# Recorder.net
KiCad netlist of a schematic drawn in EAGLE
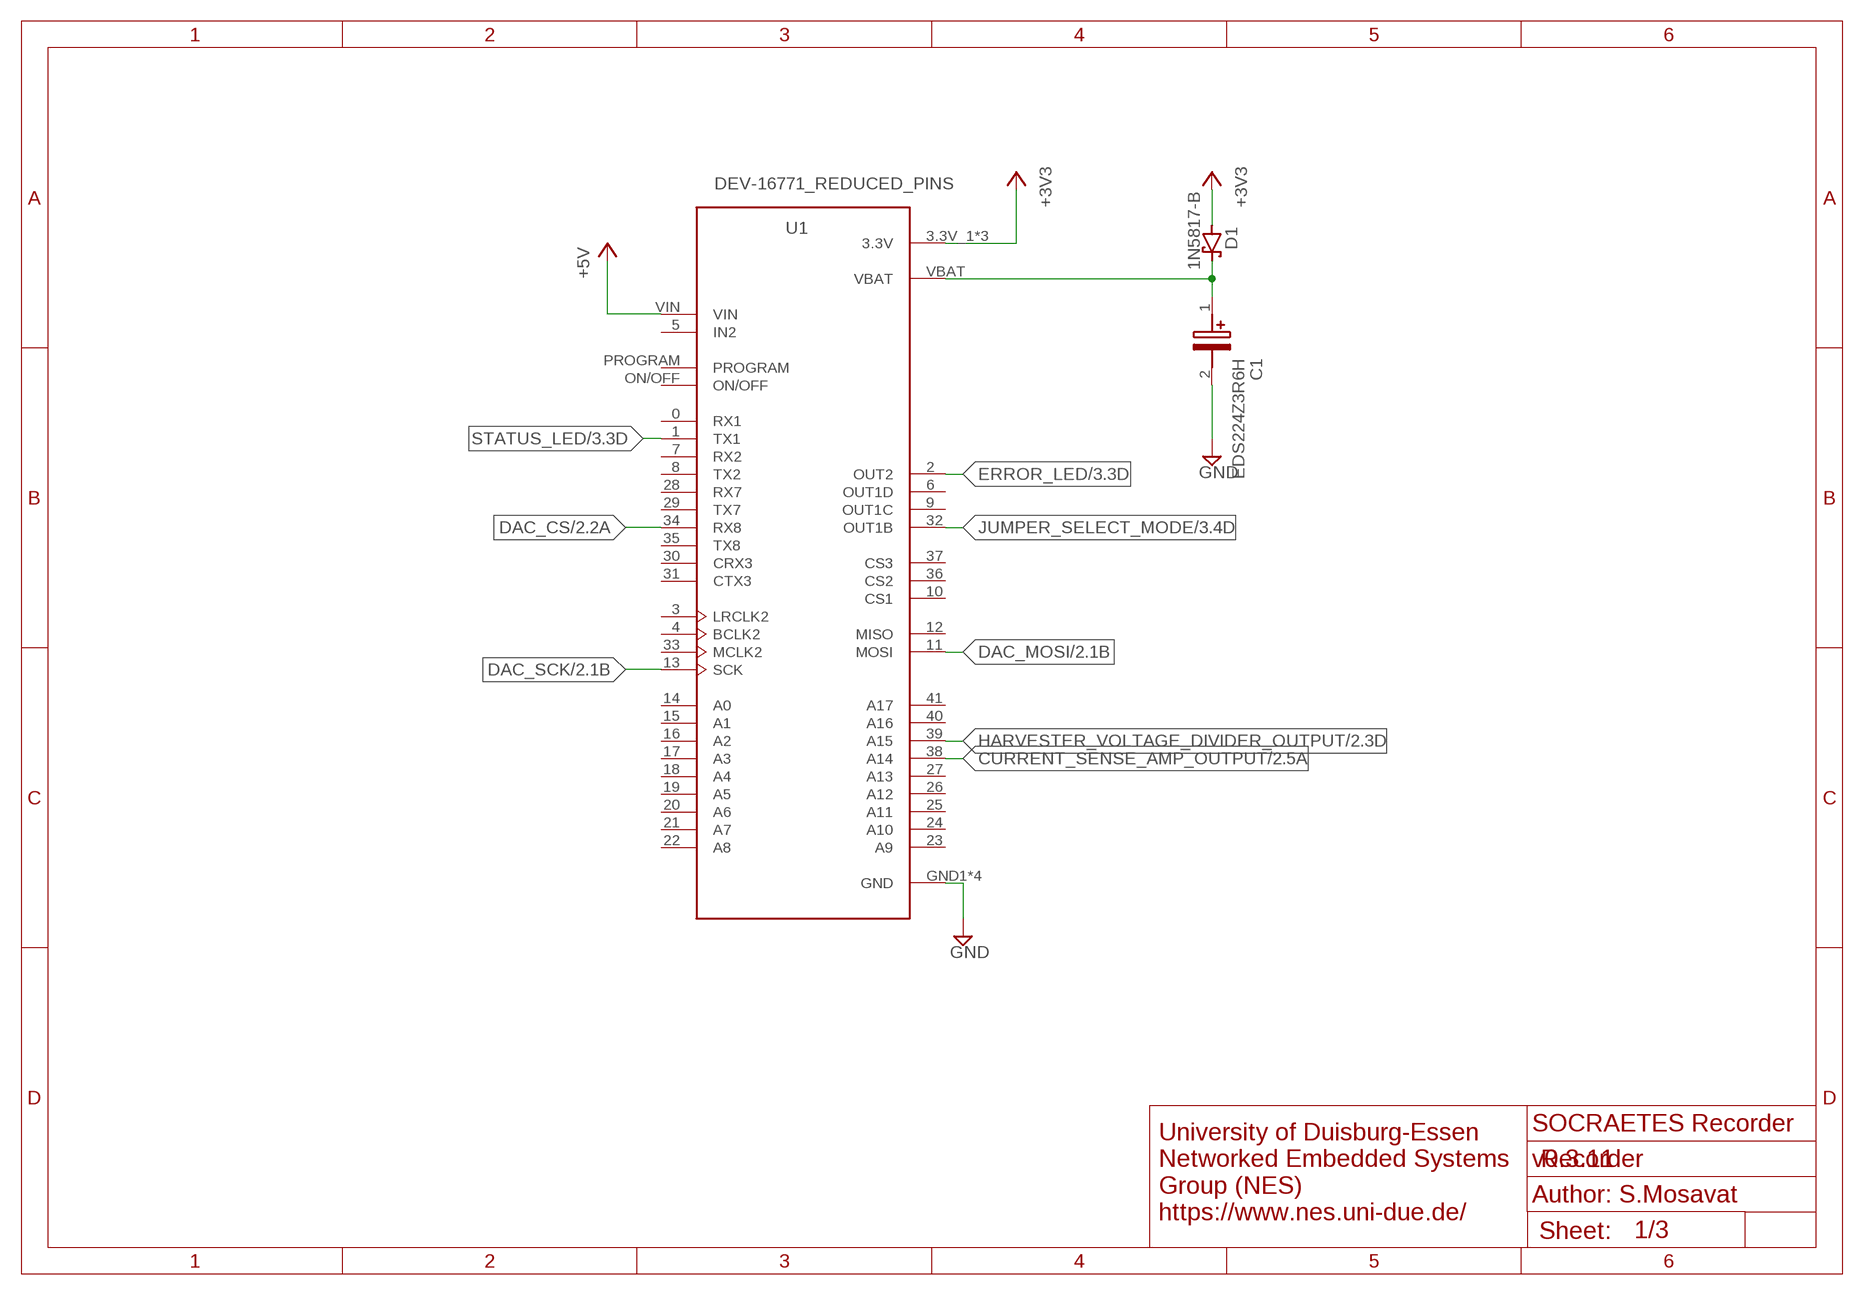
[diagram p0: schematic, sheet 1]
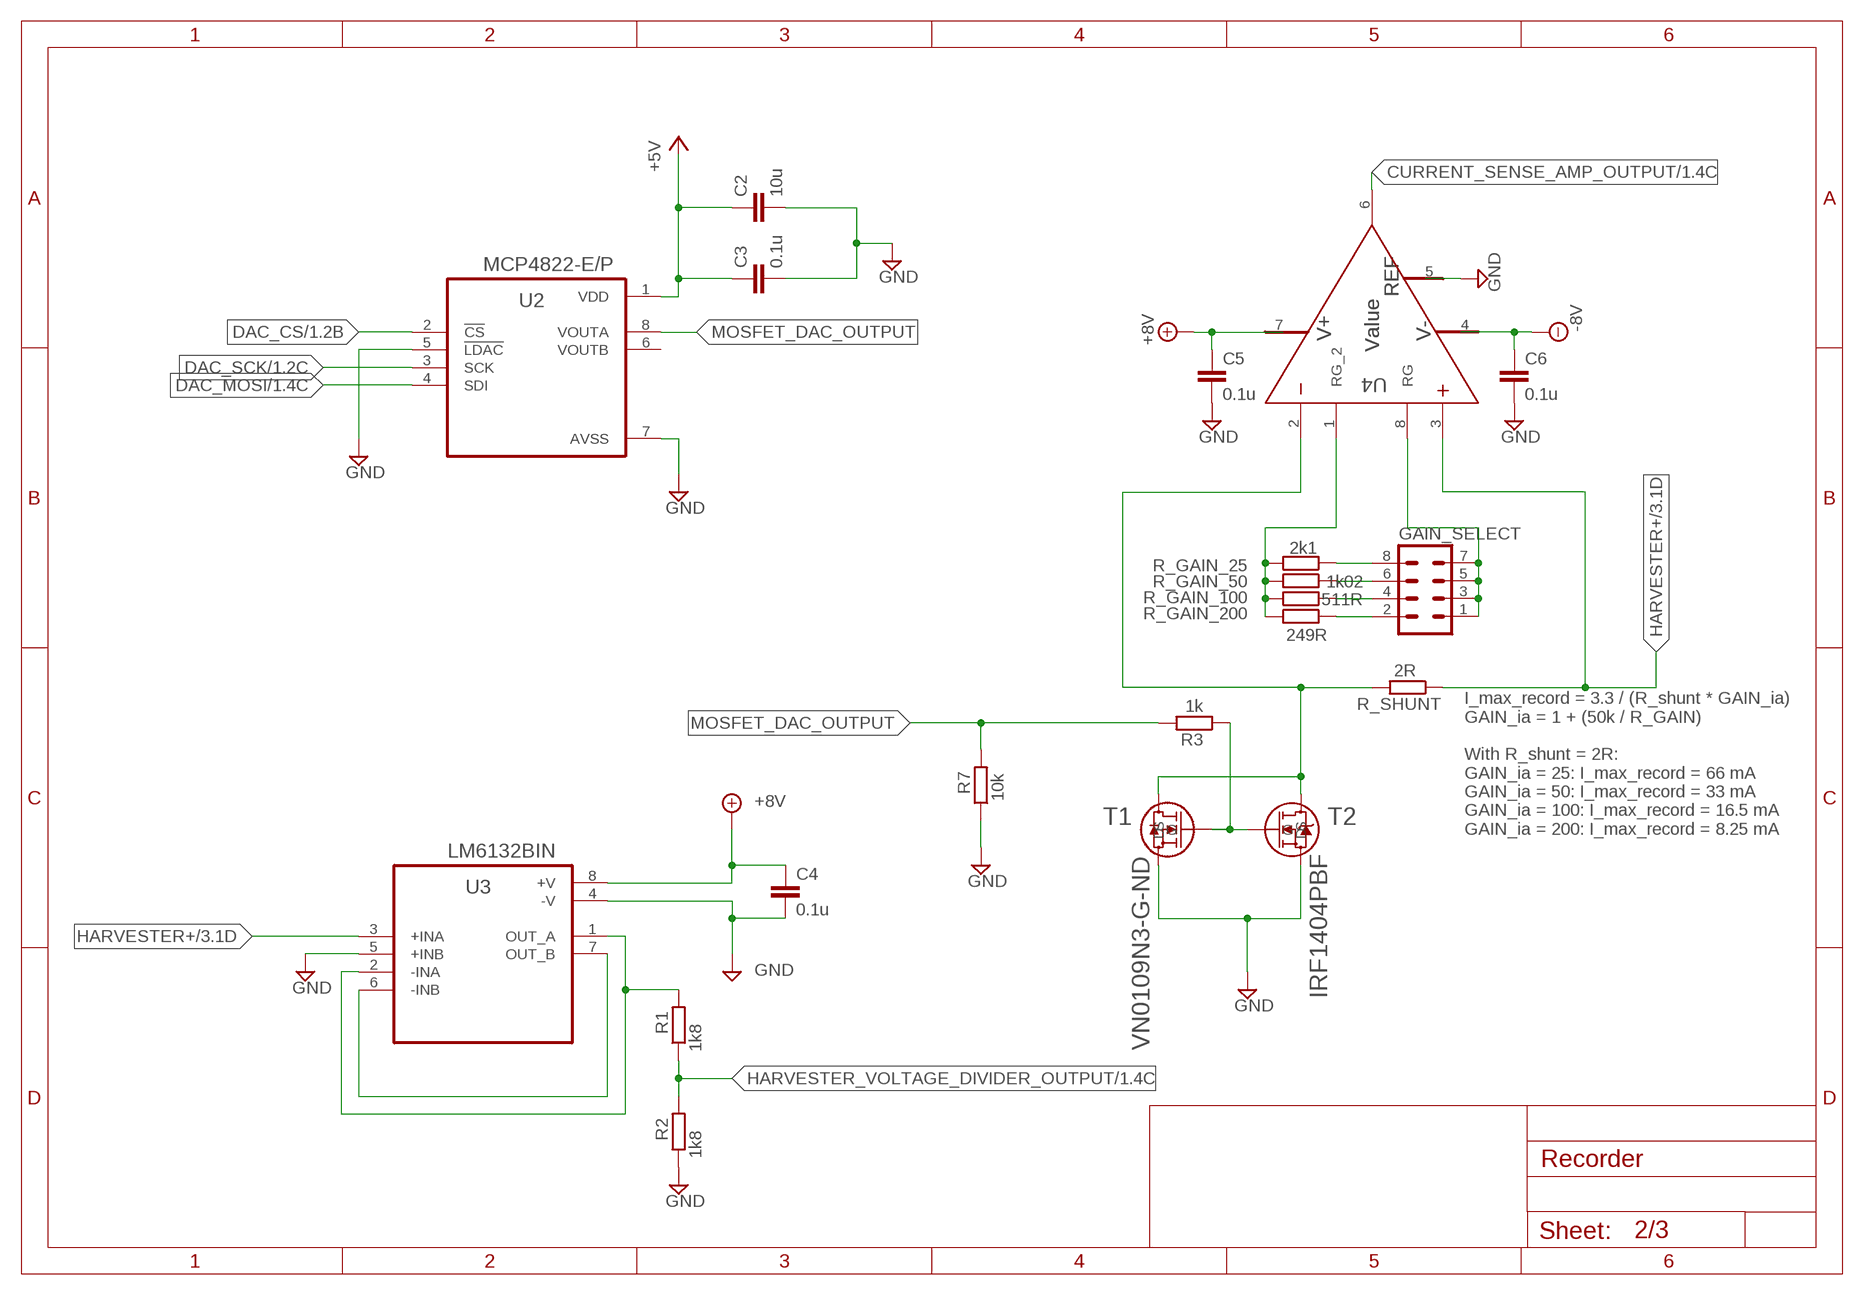
[diagram p1: schematic, sheet 2]
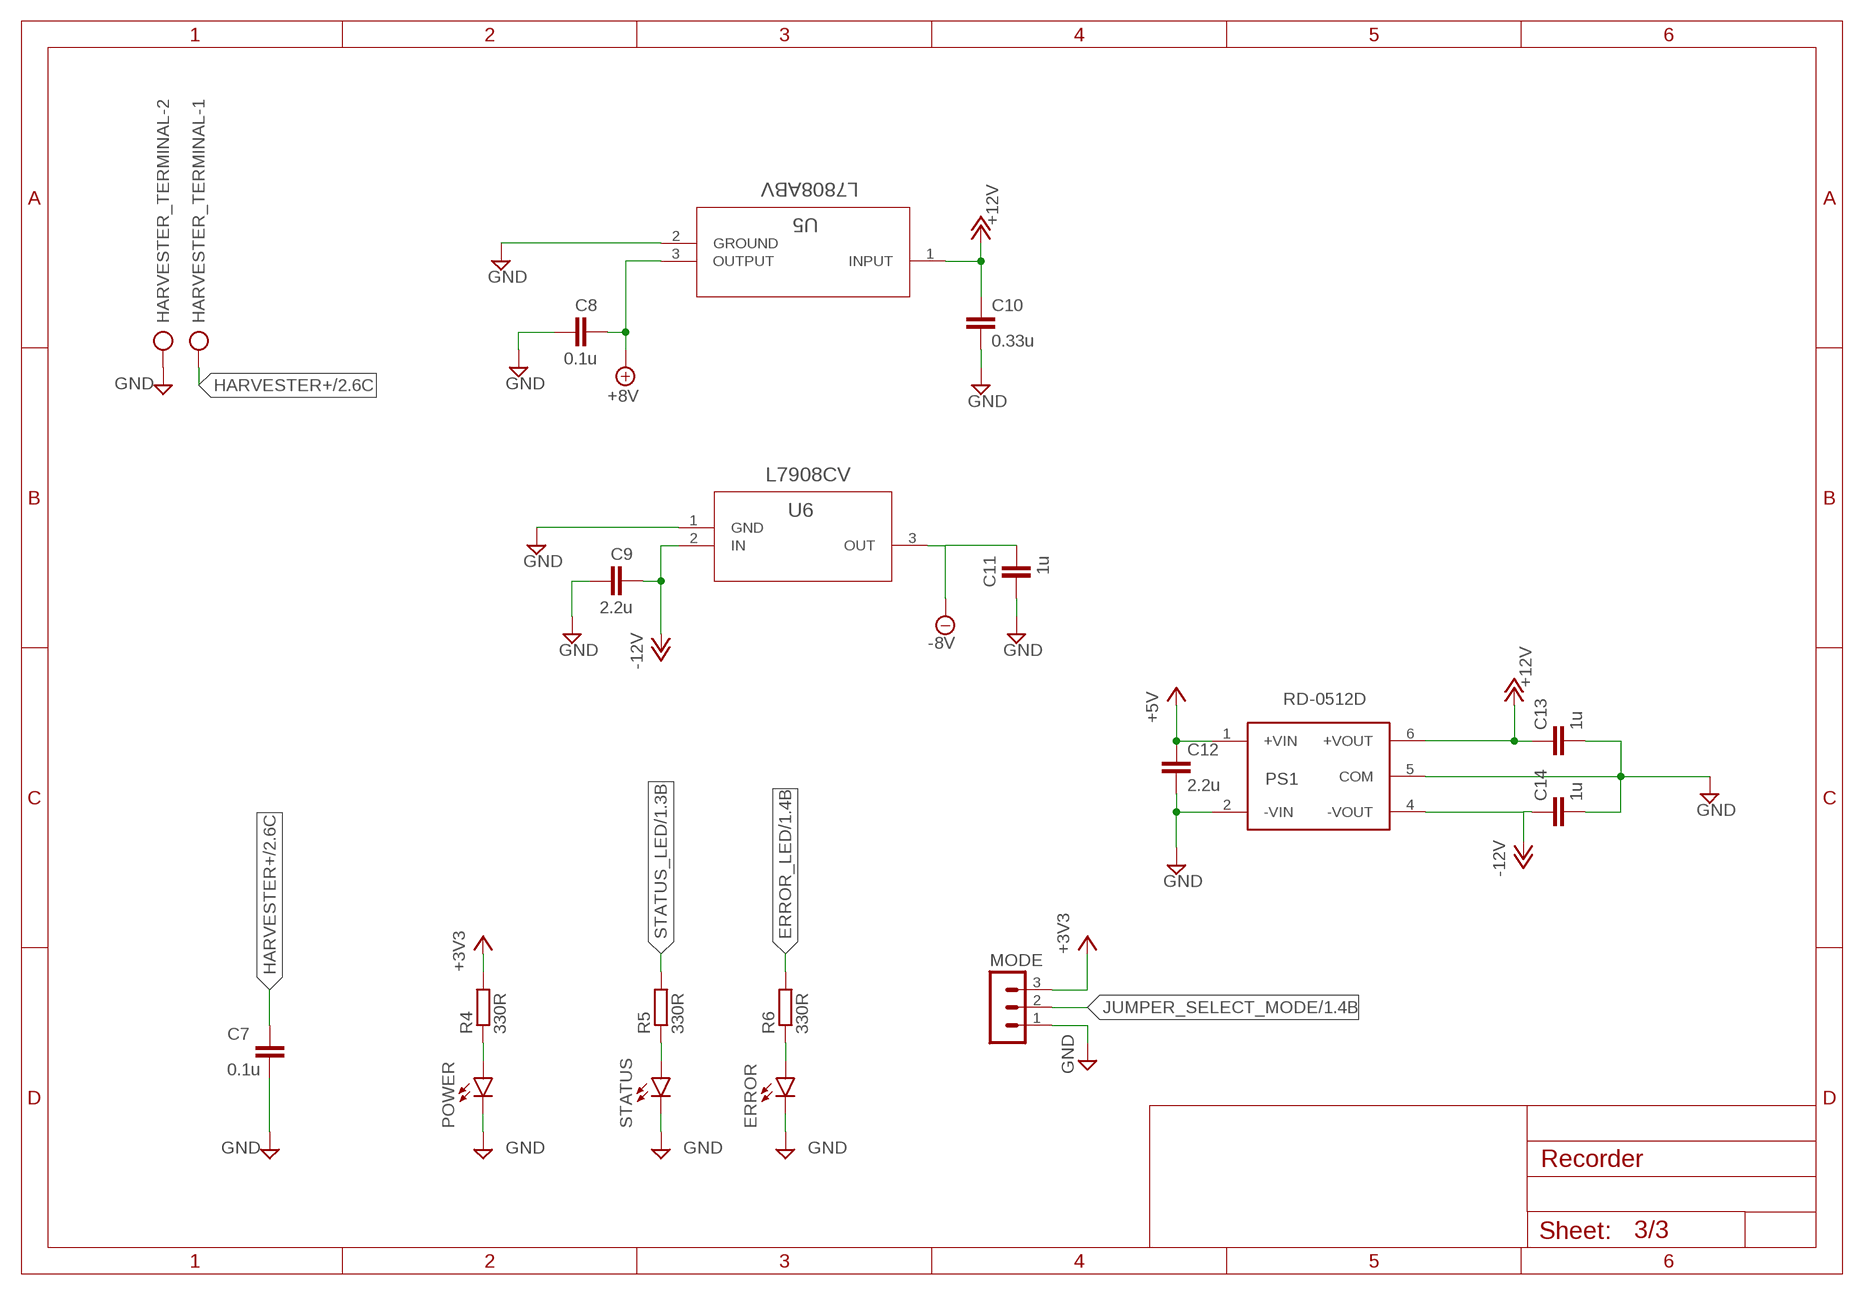
[diagram p2: schematic, sheet 3]

(export (version "E")
  (design (tool "Eeschema 10.0.6"))
  (components
    (comp (ref "C2")
      (value "10u")
      (footprint "eagle-import:C025-024X044")
      (libsource (lib "eagle-import") (part "C-EU025-024X044"))
    )
    (comp (ref "C3")
      (value "0.1u")
      (footprint "eagle-import:C025-024X044")
      (libsource (lib "eagle-import") (part "C-EU025-024X044"))
    )
    (comp (ref "C4")
      (value "0.1u")
      (footprint "eagle-import:C025-024X044")
      (libsource (lib "eagle-import") (part "C-EU025-024X044"))
    )
    (comp (ref "C5")
      (value "0.1u")
      (footprint "eagle-import:C025-024X044")
      (libsource (lib "eagle-import") (part "C-EU025-024X044"))
    )
    (comp (ref "C6")
      (value "0.1u")
      (footprint "eagle-import:C025-024X044")
      (libsource (lib "eagle-import") (part "C-EU025-024X044"))
    )
    (comp (ref "GAIN_SELECT")
      (value "MA04-2")
      (footprint "eagle-import:MA04-2")
      (libsource (lib "eagle-import") (part "MA04-2"))
    )
    (comp (ref "R1")
      (value "1k8")
      (footprint "eagle-import:0207_10")
      (libsource (lib "eagle-import") (part "R-EU_0207/10"))
    )
    (comp (ref "R2")
      (value "1k8")
      (footprint "eagle-import:0207_10")
      (libsource (lib "eagle-import") (part "R-EU_0207/10"))
    )
    (comp (ref "R3")
      (value "1k")
      (footprint "eagle-import:0207_10")
      (libsource (lib "eagle-import") (part "R-EU_0207/10"))
    )
    (comp (ref "R7")
      (value "10k")
      (footprint "eagle-import:0207_10")
      (libsource (lib "eagle-import") (part "R-EU_0207/10"))
    )
    (comp (ref "R_GAIN_25")
      (value "2k1")
      (footprint "eagle-import:0207_10")
      (libsource (lib "eagle-import") (part "R-EU_0207/10"))
    )
    (comp (ref "R_GAIN_50")
      (value "1k02")
      (footprint "eagle-import:0207_10")
      (libsource (lib "eagle-import") (part "R-EU_0207/10"))
    )
    (comp (ref "R_GAIN_100")
      (value "511R")
      (footprint "eagle-import:0207_10")
      (libsource (lib "eagle-import") (part "R-EU_0207/10"))
    )
    (comp (ref "R_GAIN_200")
      (value "249R")
      (footprint "eagle-import:0207_10")
      (libsource (lib "eagle-import") (part "R-EU_0207/10"))
    )
    (comp (ref "R_SHUNT")
      (value "2R")
      (footprint "eagle-import:0207_10")
      (libsource (lib "eagle-import") (part "R-EU_0207/10"))
    )
    (comp (ref "T1")
      (value "VN0109N3-G-ND")
      (footprint "eagle-import:TO92-CBE")
      (libsource (lib "eagle-import") (part "VN0109N3-G-ND"))
    )
    (comp (ref "T2")
      (value "IRF1404PBF")
      (footprint "eagle-import:PG-TO220-3-904_INF")
      (fields (field (name "COPYRIGHT") "Copyright (C) 2023 Ultra Librarian. All rights reserved."))
      (libsource (lib "eagle-import") (part "IRF1404PBF"))
    )
    (comp (ref "U2")
      (value "MCP4822-E/P")
      (footprint "eagle-import:DIP787W46P254L927H533Q8")
      (fields (field (name "MF") "Microchip"))
      (libsource (lib "eagle-import") (part "MCP4822-E/P"))
    )
    (comp (ref "U3")
      (value "LM6132BIN")
      (footprint "eagle-import:DIP794W45P254L959H508Q8")
      (fields
        (field (name "DIGI-KEY_PART_NUMBER") "LM6132BIN/NOPB-ND")
        (field (name "MF") "Texas Instruments")
        (field (name "MP") "LM6132BIN/NOPB")
      )
      (libsource (lib "eagle-import") (part "LM6132BIN"))
    )
    (comp (ref "U4")
      (value "Value")
      (footprint "eagle-import:P0008A")
      (fields (field (name "MANUFACTURER") "Texas Instruments") (field (name "PARTNUMBER") "INA121P"))
      (libsource (lib "eagle-import") (part "INA121PA"))
    )
    (comp (ref "C1")
      (value "EDS224Z3R6H")
      (footprint "eagle-import:EDS224Z3R6H")
      (fields (field (name "MOUSER_PART_NUMBER") "598-EDS224Z3R6H"))
      (libsource (lib "eagle-import") (part "EDS224Z3R6H"))
    )
    (comp (ref "D1")
      (value "1N5817-B")
      (footprint "eagle-import:DO41-7.6")
      (libsource (lib "eagle-import") (part "1N5817-B"))
    )
    (comp (ref "U1")
      (value "DEV-16771_REDUCED_PINS")
      (footprint "eagle-import:MODULE_DEV-16771_REDUCED_PINS")
      (libsource (lib "eagle-import") (part "DEV-16771_REDUCED_PINS"))
    )
    (comp (ref "C7")
      (value "0.1u")
      (footprint "eagle-import:C025-024X044")
      (libsource (lib "eagle-import") (part "C-EU025-024X044"))
    )
    (comp (ref "C8")
      (value "0.1u")
      (footprint "eagle-import:C025-024X044")
      (libsource (lib "eagle-import") (part "C-EU025-024X044"))
    )
    (comp (ref "C9")
      (value "2.2u")
      (footprint "eagle-import:C025-024X044")
      (libsource (lib "eagle-import") (part "C-EU025-024X044"))
    )
    (comp (ref "C10")
      (value "0.33u")
      (footprint "eagle-import:C025-024X044")
      (libsource (lib "eagle-import") (part "C-EU025-024X044"))
    )
    (comp (ref "C11")
      (value "1u")
      (footprint "eagle-import:C025-024X044")
      (libsource (lib "eagle-import") (part "C-EU025-024X044"))
    )
    (comp (ref "C12")
      (value "2.2u")
      (footprint "eagle-import:C025-024X044")
      (libsource (lib "eagle-import") (part "C-EU025-024X044"))
    )
    (comp (ref "C13")
      (value "1u")
      (footprint "eagle-import:C025-024X044")
      (libsource (lib "eagle-import") (part "C-EU025-024X044"))
    )
    (comp (ref "C14")
      (value "1u")
      (footprint "eagle-import:C025-024X044")
      (libsource (lib "eagle-import") (part "C-EU025-024X044"))
    )
    (comp (ref "ERROR")
      (value "LED5MM")
      (footprint "eagle-import:LED5MM")
      (libsource (lib "eagle-import") (part "LED5MM"))
    )
    (comp (ref "HARVESTER_TERMINAL")
      (value "AK300/2")
      (footprint "eagle-import:AK300_2")
      (libsource (lib "eagle-import") (part "AK300/2"))
    )
    (comp (ref "MODE")
      (value "MA03-1")
      (footprint "eagle-import:MA03-1")
      (libsource (lib "eagle-import") (part "MA03-1"))
    )
    (comp (ref "POWER")
      (value "LED5MM")
      (footprint "eagle-import:LED5MM")
      (libsource (lib "eagle-import") (part "LED5MM"))
    )
    (comp (ref "PS1")
      (value "RD-0512D")
      (footprint "eagle-import:CONV_RD-0512D")
      (fields (field (name "MF") "Recom Power"))
      (libsource (lib "eagle-import") (part "RD-0512D"))
    )
    (comp (ref "R4")
      (value "330R")
      (footprint "eagle-import:0207_10")
      (libsource (lib "eagle-import") (part "R-EU_0207/10"))
    )
    (comp (ref "R5")
      (value "330R")
      (footprint "eagle-import:0207_10")
      (libsource (lib "eagle-import") (part "R-EU_0207/10"))
    )
    (comp (ref "R6")
      (value "330R")
      (footprint "eagle-import:0207_10")
      (libsource (lib "eagle-import") (part "R-EU_0207/10"))
    )
    (comp (ref "STATUS")
      (value "LED5MM")
      (footprint "eagle-import:LED5MM")
      (libsource (lib "eagle-import") (part "LED5MM"))
    )
    (comp (ref "U5")
      (value "L7808ABV")
      (footprint "eagle-import:TO-220_STM")
      (libsource (lib "eagle-import") (part "L7808ABV"))
    )
    (comp (ref "U6")
      (value "L7908CV")
      (footprint "eagle-import:TO-220_STM")
      (libsource (lib "eagle-import") (part "L7908CV"))
    )
  )
  (nets
    (net (code "1") (name "+3V3") (class "Default")
      (node (ref "D1") (pin "A") (pinfunction "A_A") (pintype "passive"))
      (node (ref "MODE") (pin "3") (pinfunction "3_3") (pintype "passive"))
      (node (ref "R4") (pin "2") (pinfunction "2_2") (pintype "passive"))
      (node (ref "U1") (pin "3.3V_1") (pinfunction "3.3V_3.3V_1") (pintype "power_in"))
      (node (ref "U1") (pin "3.3V_2") (pinfunction "3.3V_3.3V_2") (pintype "power_in"))
      (node (ref "U1") (pin "3.3V_3") (pinfunction "3.3V_3.3V_3") (pintype "power_in"))
    )
    (net (code "2") (name "+5V") (class "Default")
      (node (ref "C12") (pin "1") (pinfunction "1_1") (pintype "passive"))
      (node (ref "C2") (pin "1") (pinfunction "1_1") (pintype "passive"))
      (node (ref "C3") (pin "1") (pinfunction "1_1") (pintype "passive"))
      (node (ref "PS1") (pin "1") (pinfunction "+VIN_1") (pintype "input"))
      (node (ref "U1") (pin "VIN") (pinfunction "VIN_VIN") (pintype "input"))
      (node (ref "U2") (pin "1") (pinfunction "VDD_1") (pintype "power_in"))
    )
    (net (code "3") (name "+8V") (class "Default")
      (node (ref "C4") (pin "1") (pinfunction "1_1") (pintype "passive"))
      (node (ref "C5") (pin "1") (pinfunction "1_1") (pintype "passive"))
      (node (ref "C8") (pin "2") (pinfunction "2_2") (pintype "passive"))
      (node (ref "U3") (pin "8") (pinfunction "+V_8") (pintype "power_in"))
      (node (ref "U4") (pin "7") (pinfunction "V+_7") (pintype "power_in"))
      (node (ref "U5") (pin "3") (pinfunction "OUTPUT_3") (pintype "output"))
    )
    (net (code "4") (name "+12V") (class "Default")
      (node (ref "C10") (pin "1") (pinfunction "1_1") (pintype "passive"))
      (node (ref "C13") (pin "1") (pinfunction "1_1") (pintype "passive"))
      (node (ref "PS1") (pin "6") (pinfunction "+VOUT_6") (pintype "output"))
      (node (ref "U5") (pin "1") (pinfunction "INPUT_1") (pintype "input"))
    )
    (net (code "5") (name "-8V") (class "Default")
      (node (ref "C11") (pin "2") (pinfunction "2_2") (pintype "passive"))
      (node (ref "C6") (pin "1") (pinfunction "1_1") (pintype "passive"))
      (node (ref "U4") (pin "4") (pinfunction "V-_4") (pintype "power_in"))
      (node (ref "U6") (pin "3") (pinfunction "OUT_3") (pintype "power_in"))
    )
    (net (code "6") (name "-12V") (class "Default")
      (node (ref "C14") (pin "1") (pinfunction "1_1") (pintype "passive"))
      (node (ref "C9") (pin "2") (pinfunction "2_2") (pintype "passive"))
      (node (ref "PS1") (pin "4") (pinfunction "-VOUT_4") (pintype "output"))
      (node (ref "U6") (pin "2") (pinfunction "IN_2") (pintype "power_in"))
    )
    (net (code "7") (name "CURRENT_SENSE_AMP_OUTPUT") (class "Default")
      (node (ref "U1") (pin "38") (pinfunction "A14_38") (pintype "bidirectional"))
      (node (ref "U4") (pin "6") (pinfunction "OUT_6") (pintype "output"))
    )
    (net (code "8") (name "DAC_CS") (class "Default")
      (node (ref "U1") (pin "34") (pinfunction "RX8_34") (pintype "bidirectional"))
      (node (ref "U2") (pin "2") (pinfunction "~{CS}_2") (pintype "input"))
    )
    (net (code "9") (name "DAC_MOSI") (class "Default")
      (node (ref "U1") (pin "11") (pinfunction "MOSI_11") (pintype "bidirectional"))
      (node (ref "U2") (pin "4") (pinfunction "SDI_4") (pintype "input"))
    )
    (net (code "10") (name "DAC_SCK") (class "Default")
      (node (ref "U1") (pin "13") (pinfunction "SCK_13") (pintype "bidirectional"))
      (node (ref "U2") (pin "3") (pinfunction "SCK_3") (pintype "input"))
    )
    (net (code "11") (name "ERROR_LED") (class "Default")
      (node (ref "R6") (pin "2") (pinfunction "2_2") (pintype "passive"))
      (node (ref "U1") (pin "2") (pinfunction "OUT2_2") (pintype "output"))
    )
    (net (code "12") (name "GND") (class "Default")
      (node (ref "C1") (pin "2") (pinfunction "-_2") (pintype "bidirectional"))
      (node (ref "C10") (pin "2") (pinfunction "2_2") (pintype "passive"))
      (node (ref "C11") (pin "1") (pinfunction "1_1") (pintype "passive"))
      (node (ref "C12") (pin "2") (pinfunction "2_2") (pintype "passive"))
      (node (ref "C13") (pin "2") (pinfunction "2_2") (pintype "passive"))
      (node (ref "C14") (pin "2") (pinfunction "2_2") (pintype "passive"))
      (node (ref "C2") (pin "2") (pinfunction "2_2") (pintype "passive"))
      (node (ref "C3") (pin "2") (pinfunction "2_2") (pintype "passive"))
      (node (ref "C4") (pin "2") (pinfunction "2_2") (pintype "passive"))
      (node (ref "C5") (pin "2") (pinfunction "2_2") (pintype "passive"))
      (node (ref "C6") (pin "2") (pinfunction "2_2") (pintype "passive"))
      (node (ref "C7") (pin "2") (pinfunction "2_2") (pintype "passive"))
      (node (ref "C8") (pin "1") (pinfunction "1_1") (pintype "passive"))
      (node (ref "C9") (pin "1") (pinfunction "1_1") (pintype "passive"))
      (node (ref "ERROR") (pin "K") (pinfunction "C_K") (pintype "passive"))
      (node (ref "HARVESTER_TERMINAL") (pin "2") (pinfunction "KL_2") (pintype "passive"))
      (node (ref "MODE") (pin "1") (pinfunction "1_1") (pintype "passive"))
      (node (ref "POWER") (pin "K") (pinfunction "C_K") (pintype "passive"))
      (node (ref "PS1") (pin "2") (pinfunction "-VIN_2") (pintype "input"))
      (node (ref "PS1") (pin "5") (pinfunction "COM_5") (pintype "power_in"))
      (node (ref "R2") (pin "1") (pinfunction "1_1") (pintype "passive"))
      (node (ref "R7") (pin "1") (pinfunction "1_1") (pintype "passive"))
      (node (ref "STATUS") (pin "K") (pinfunction "C_K") (pintype "passive"))
      (node (ref "T1") (pin "SOURCE") (pinfunction "S_SOURCE") (pintype "passive"))
      (node (ref "T2") (pin "S") (pinfunction "S_S") (pintype "passive"))
      (node (ref "U1") (pin "GND1") (pinfunction "GND_GND1") (pintype "power_in"))
      (node (ref "U1") (pin "GND2") (pinfunction "GND_GND2") (pintype "power_in"))
      (node (ref "U1") (pin "GND3") (pinfunction "GND_GND3") (pintype "power_in"))
      (node (ref "U1") (pin "GND4") (pinfunction "GND_GND4") (pintype "power_in"))
      (node (ref "U2") (pin "5") (pinfunction "~{LDAC}_5") (pintype "input"))
      (node (ref "U2") (pin "7") (pinfunction "AVSS_7") (pintype "power_in"))
      (node (ref "U3") (pin "4") (pinfunction "-V_4") (pintype "power_in"))
      (node (ref "U3") (pin "5") (pinfunction "+INB_5") (pintype "input"))
      (node (ref "U4") (pin "5") (pinfunction "REF_5") (pintype "input"))
      (node (ref "U5") (pin "2") (pinfunction "GROUND_2") (pintype "passive"))
      (node (ref "U6") (pin "1") (pinfunction "GND_1") (pintype "power_in"))
    )
    (net (code "13") (name "HARVESTER+") (class "Default")
      (node (ref "C7") (pin "1") (pinfunction "1_1") (pintype "passive"))
      (node (ref "HARVESTER_TERMINAL") (pin "1") (pinfunction "KL_1") (pintype "passive"))
      (node (ref "R_SHUNT") (pin "1") (pinfunction "1_1") (pintype "passive"))
      (node (ref "U3") (pin "3") (pinfunction "+INA_3") (pintype "input"))
      (node (ref "U4") (pin "3") (pinfunction "IN+_3") (pintype "input"))
    )
    (net (code "14") (name "HARVESTER_VOLTAGE_DIVIDER_OUTPUT") (class "Default")
      (node (ref "R1") (pin "1") (pinfunction "1_1") (pintype "passive"))
      (node (ref "R2") (pin "2") (pinfunction "2_2") (pintype "passive"))
      (node (ref "U1") (pin "39") (pinfunction "A15_39") (pintype "bidirectional"))
    )
    (net (code "15") (name "JUMPER_SELECT_MODE") (class "Default")
      (node (ref "MODE") (pin "2") (pinfunction "2_2") (pintype "passive"))
      (node (ref "U1") (pin "32") (pinfunction "OUT1B_32") (pintype "output"))
    )
    (net (code "16") (name "MOSFET_DAC_OUTPUT") (class "Default")
      (node (ref "R3") (pin "2") (pinfunction "2_2") (pintype "passive"))
      (node (ref "R7") (pin "2") (pinfunction "2_2") (pintype "passive"))
      (node (ref "U2") (pin "8") (pinfunction "VOUTA_8") (pintype "output"))
    )
    (net (code "17") (name "Net-(C1-+)") (class "Default")
      (node (ref "C1") (pin "1") (pinfunction "+_1") (pintype "bidirectional"))
      (node (ref "D1") (pin "C") (pinfunction "C_C") (pintype "passive"))
      (node (ref "U1") (pin "VBAT") (pinfunction "VBAT_VBAT") (pintype "passive"))
    )
    (net (code "18") (name "Net-(ERROR-PadA)") (class "Default")
      (node (ref "ERROR") (pin "A") (pinfunction "A_A") (pintype "passive"))
      (node (ref "R6") (pin "1") (pinfunction "1_1") (pintype "passive"))
    )
    (net (code "19") (name "Net-(GAIN_SELECT-Pad2)") (class "Default")
      (node (ref "GAIN_SELECT") (pin "2") (pinfunction "2_2") (pintype "passive"))
      (node (ref "R_GAIN_200") (pin "1") (pinfunction "1_1") (pintype "passive"))
    )
    (net (code "20") (name "Net-(GAIN_SELECT-Pad4)") (class "Default")
      (node (ref "GAIN_SELECT") (pin "4") (pinfunction "4_4") (pintype "passive"))
      (node (ref "R_GAIN_100") (pin "1") (pinfunction "1_1") (pintype "passive"))
    )
    (net (code "21") (name "Net-(GAIN_SELECT-Pad6)") (class "Default")
      (node (ref "GAIN_SELECT") (pin "6") (pinfunction "6_6") (pintype "passive"))
      (node (ref "R_GAIN_50") (pin "1") (pinfunction "1_1") (pintype "passive"))
    )
    (net (code "22") (name "Net-(GAIN_SELECT-Pad8)") (class "Default")
      (node (ref "GAIN_SELECT") (pin "8") (pinfunction "8_8") (pintype "passive"))
      (node (ref "R_GAIN_25") (pin "1") (pinfunction "1_1") (pintype "passive"))
    )
    (net (code "23") (name "Net-(POWER-PadA)") (class "Default")
      (node (ref "POWER") (pin "A") (pinfunction "A_A") (pintype "passive"))
      (node (ref "R4") (pin "1") (pinfunction "1_1") (pintype "passive"))
    )
    (net (code "24") (name "Net-(R5-Pad1)") (class "Default")
      (node (ref "R5") (pin "1") (pinfunction "1_1") (pintype "passive"))
      (node (ref "STATUS") (pin "A") (pinfunction "A_A") (pintype "passive"))
    )
    (net (code "25") (name "Net-(T1-D)") (class "Default")
      (node (ref "R_SHUNT") (pin "2") (pinfunction "2_2") (pintype "passive"))
      (node (ref "T1") (pin "DRAIN") (pinfunction "D_DRAIN") (pintype "passive"))
      (node (ref "T2") (pin "D") (pinfunction "D_D") (pintype "passive"))
      (node (ref "U4") (pin "2") (pinfunction "IN-_2") (pintype "input"))
    )
    (net (code "26") (name "Net-(T1-G)") (class "Default")
      (node (ref "R3") (pin "1") (pinfunction "1_1") (pintype "passive"))
      (node (ref "T1") (pin "GATE") (pinfunction "G_GATE") (pintype "passive"))
      (node (ref "T2") (pin "G") (pinfunction "G_G") (pintype "passive"))
    )
    (net (code "27") (name "Net-(U3--INA)") (class "Default")
      (node (ref "R1") (pin "2") (pinfunction "2_2") (pintype "passive"))
      (node (ref "U3") (pin "1") (pinfunction "OUT_A_1") (pintype "output"))
      (node (ref "U3") (pin "2") (pinfunction "-INA_2") (pintype "input"))
    )
    (net (code "28") (name "Net-(U3--INB)") (class "Default")
      (node (ref "U3") (pin "6") (pinfunction "-INB_6") (pintype "input"))
      (node (ref "U3") (pin "7") (pinfunction "OUT_B_7") (pintype "output"))
    )
    (net (code "29") (name "Net-(U4-RG)") (class "Default")
      (node (ref "GAIN_SELECT") (pin "1") (pinfunction "1_1") (pintype "passive"))
      (node (ref "GAIN_SELECT") (pin "3") (pinfunction "3_3") (pintype "passive"))
      (node (ref "GAIN_SELECT") (pin "5") (pinfunction "5_5") (pintype "passive"))
      (node (ref "GAIN_SELECT") (pin "7") (pinfunction "7_7") (pintype "passive"))
      (node (ref "U4") (pin "8") (pinfunction "RG_8") (pintype "passive"))
    )
    (net (code "30") (name "Net-(U4-RG_2)") (class "Default")
      (node (ref "R_GAIN_100") (pin "2") (pinfunction "2_2") (pintype "passive"))
      (node (ref "R_GAIN_200") (pin "2") (pinfunction "2_2") (pintype "passive"))
      (node (ref "R_GAIN_25") (pin "2") (pinfunction "2_2") (pintype "passive"))
      (node (ref "R_GAIN_50") (pin "2") (pinfunction "2_2") (pintype "passive"))
      (node (ref "U4") (pin "1") (pinfunction "RG_2_1") (pintype "passive"))
    )
    (net (code "31") (name "STATUS_LED") (class "Default")
      (node (ref "R5") (pin "2") (pinfunction "2_2") (pintype "passive"))
      (node (ref "U1") (pin "1") (pinfunction "TX1_1") (pintype "bidirectional"))
    )
    (net (code "32") (name "unconnected-(U1-A0-Pad14)") (class "Default")
      (node (ref "U1") (pin "14") (pinfunction "A0_14") (pintype "bidirectional"))
    )
    (net (code "33") (name "unconnected-(U1-A1-Pad15)") (class "Default")
      (node (ref "U1") (pin "15") (pinfunction "A1_15") (pintype "bidirectional"))
    )
    (net (code "34") (name "unconnected-(U1-A2-Pad16)") (class "Default")
      (node (ref "U1") (pin "16") (pinfunction "A2_16") (pintype "bidirectional"))
    )
    (net (code "35") (name "unconnected-(U1-A3-Pad17)") (class "Default")
      (node (ref "U1") (pin "17") (pinfunction "A3_17") (pintype "bidirectional"))
    )
    (net (code "36") (name "unconnected-(U1-A4-Pad18)") (class "Default")
      (node (ref "U1") (pin "18") (pinfunction "A4_18") (pintype "bidirectional"))
    )
    (net (code "37") (name "unconnected-(U1-A5-Pad19)") (class "Default")
      (node (ref "U1") (pin "19") (pinfunction "A5_19") (pintype "bidirectional"))
    )
    (net (code "38") (name "unconnected-(U1-A6-Pad20)") (class "Default")
      (node (ref "U1") (pin "20") (pinfunction "A6_20") (pintype "bidirectional"))
    )
    (net (code "39") (name "unconnected-(U1-A7-Pad21)") (class "Default")
      (node (ref "U1") (pin "21") (pinfunction "A7_21") (pintype "bidirectional"))
    )
    (net (code "40") (name "unconnected-(U1-A8-Pad22)") (class "Default")
      (node (ref "U1") (pin "22") (pinfunction "A8_22") (pintype "bidirectional"))
    )
    (net (code "41") (name "unconnected-(U1-A9-Pad23)") (class "Default")
      (node (ref "U1") (pin "23") (pinfunction "A9_23") (pintype "bidirectional"))
    )
    (net (code "42") (name "unconnected-(U1-A10-Pad24)") (class "Default")
      (node (ref "U1") (pin "24") (pinfunction "A10_24") (pintype "bidirectional"))
    )
    (net (code "43") (name "unconnected-(U1-A11-Pad25)") (class "Default")
      (node (ref "U1") (pin "25") (pinfunction "A11_25") (pintype "bidirectional"))
    )
    (net (code "44") (name "unconnected-(U1-A12-Pad26)") (class "Default")
      (node (ref "U1") (pin "26") (pinfunction "A12_26") (pintype "bidirectional"))
    )
    (net (code "45") (name "unconnected-(U1-A13-Pad27)") (class "Default")
      (node (ref "U1") (pin "27") (pinfunction "A13_27") (pintype "bidirectional"))
    )
    (net (code "46") (name "unconnected-(U1-A16-Pad40)") (class "Default")
      (node (ref "U1") (pin "40") (pinfunction "A16_40") (pintype "bidirectional"))
    )
    (net (code "47") (name "unconnected-(U1-A17-Pad41)") (class "Default")
      (node (ref "U1") (pin "41") (pinfunction "A17_41") (pintype "bidirectional"))
    )
    (net (code "48") (name "unconnected-(U1-BCLK2-Pad4)") (class "Default")
      (node (ref "U1") (pin "4") (pinfunction "BCLK2_4") (pintype "bidirectional"))
    )
    (net (code "49") (name "unconnected-(U1-CRX3-Pad30)") (class "Default")
      (node (ref "U1") (pin "30") (pinfunction "CRX3_30") (pintype "bidirectional"))
    )
    (net (code "50") (name "unconnected-(U1-CS1-Pad10)") (class "Default")
      (node (ref "U1") (pin "10") (pinfunction "CS1_10") (pintype "bidirectional"))
    )
    (net (code "51") (name "unconnected-(U1-CS2-Pad36)") (class "Default")
      (node (ref "U1") (pin "36") (pinfunction "CS2_36") (pintype "bidirectional"))
    )
    (net (code "52") (name "unconnected-(U1-CS3-Pad37)") (class "Default")
      (node (ref "U1") (pin "37") (pinfunction "CS3_37") (pintype "bidirectional"))
    )
    (net (code "53") (name "unconnected-(U1-CTX3-Pad31)") (class "Default")
      (node (ref "U1") (pin "31") (pinfunction "CTX3_31") (pintype "bidirectional"))
    )
    (net (code "54") (name "unconnected-(U1-IN2-Pad5)") (class "Default")
      (node (ref "U1") (pin "5") (pinfunction "IN2_5") (pintype "bidirectional"))
    )
    (net (code "55") (name "unconnected-(U1-LRCLK2-Pad3)") (class "Default")
      (node (ref "U1") (pin "3") (pinfunction "LRCLK2_3") (pintype "bidirectional"))
    )
    (net (code "56") (name "unconnected-(U1-MCLK2-Pad33)") (class "Default")
      (node (ref "U1") (pin "33") (pinfunction "MCLK2_33") (pintype "bidirectional"))
    )
    (net (code "57") (name "unconnected-(U1-MISO-Pad12)") (class "Default")
      (node (ref "U1") (pin "12") (pinfunction "MISO_12") (pintype "bidirectional"))
    )
    (net (code "58") (name "unconnected-(U1-OUT1C-Pad9)") (class "Default")
      (node (ref "U1") (pin "9") (pinfunction "OUT1C_9") (pintype "output"))
    )
    (net (code "59") (name "unconnected-(U1-OUT1D-Pad6)") (class "Default")
      (node (ref "U1") (pin "6") (pinfunction "OUT1D_6") (pintype "output"))
    )
    (net (code "60") (name "unconnected-(U1-PadON{slash}OFF)") (class "Default")
      (node (ref "U1") (pin "ON/OFF") (pinfunction "ON/OFF_ON/OFF") (pintype "bidirectional"))
    )
    (net (code "61") (name "unconnected-(U1-PadPROGRAM)") (class "Default")
      (node (ref "U1") (pin "PROGRAM") (pinfunction "PROGRAM_PROGRAM") (pintype "bidirectional"))
    )
    (net (code "62") (name "unconnected-(U1-RX1-Pad0)") (class "Default")
      (node (ref "U1") (pin "0") (pinfunction "RX1_0") (pintype "bidirectional"))
    )
    (net (code "63") (name "unconnected-(U1-RX2-Pad7)") (class "Default")
      (node (ref "U1") (pin "7") (pinfunction "RX2_7") (pintype "bidirectional"))
    )
    (net (code "64") (name "unconnected-(U1-RX7-Pad28)") (class "Default")
      (node (ref "U1") (pin "28") (pinfunction "RX7_28") (pintype "bidirectional"))
    )
    (net (code "65") (name "unconnected-(U1-TX2-Pad8)") (class "Default")
      (node (ref "U1") (pin "8") (pinfunction "TX2_8") (pintype "bidirectional"))
    )
    (net (code "66") (name "unconnected-(U1-TX7-Pad29)") (class "Default")
      (node (ref "U1") (pin "29") (pinfunction "TX7_29") (pintype "bidirectional"))
    )
    (net (code "67") (name "unconnected-(U1-TX8-Pad35)") (class "Default")
      (node (ref "U1") (pin "35") (pinfunction "TX8_35") (pintype "bidirectional"))
    )
    (net (code "68") (name "unconnected-(U2-VOUTB-Pad6)") (class "Default")
      (node (ref "U2") (pin "6") (pinfunction "VOUTB_6") (pintype "output"))
    )
  )
)
